# CAN_MUX.net
KiCad netlist of a schematic drawn in Altium Designer
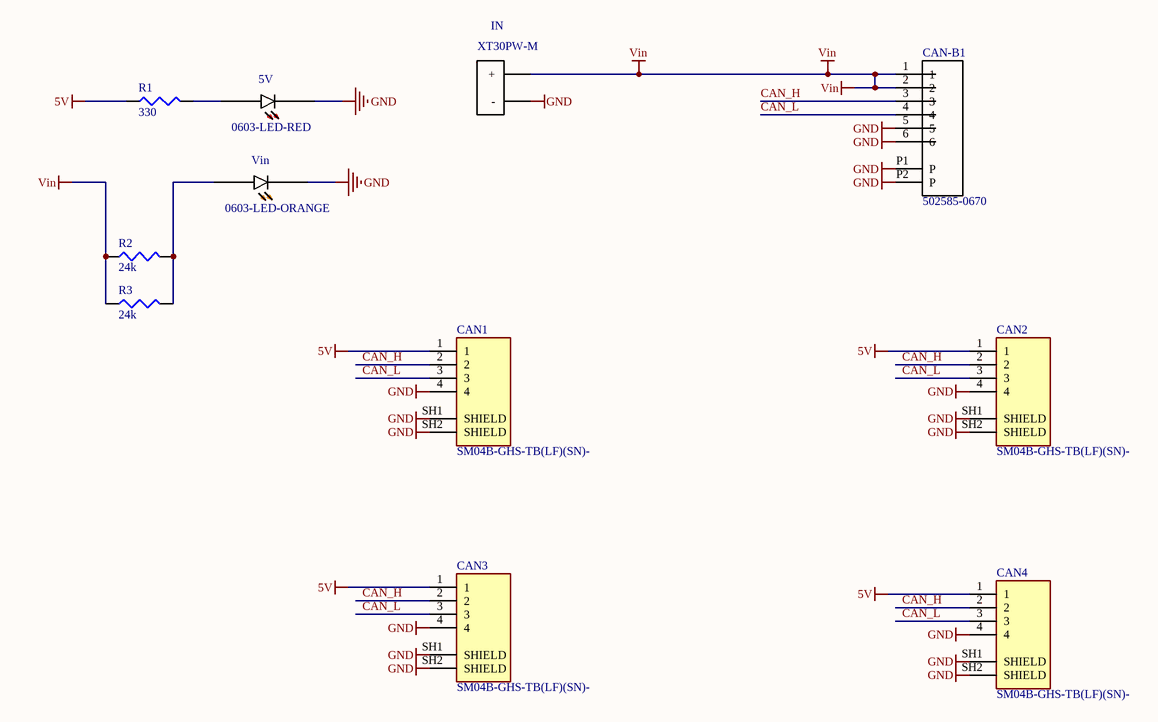
[diagram p0: CAN MUX.SchDoc]

(export (version "E")
  (design (tool "Eeschema 10.0.6"))
  (components
    (comp (ref "5V")
      (value "0603-LED-RED")
      (footprint "*LEDM1608X80_LTE-C1906R-14(Primary)")
      (description "Red 620nm LED Indication - Discrete 2.2V 0603 (1608 Metric)")
      (fields (field (name "MP") "LTST-C194KRKT"))
      (libsource (lib "lib") (part "0603-LED-RED"))
    )
    (comp (ref "CAN-B1")
      (value "502585-0670")
      (footprint "MOLEX_502585-0670")
      (fields (field (name "MF") "Molex"))
      (libsource (lib "lib") (part "502585-0670"))
    )
    (comp (ref "CAN1")
      (value "SM04B-GHS-TB(LF)(SN)-")
      (footprint "JST_SM04B-GHS-TB(LF)(SN)-")
      (description "Connector Header Surface Mount, Right Angle 4 position 0.049 _1.25mm_")
      (fields (field (name "MP") "SM04B-GHS-TB_LF__SN_-") (field (name "MF") "JST Sales"))
      (libsource (lib "lib") (part "SM04B-GHS-TB(LF)(SN)-"))
    )
    (comp (ref "CAN2")
      (value "SM04B-GHS-TB(LF)(SN)-")
      (footprint "JST_SM04B-GHS-TB(LF)(SN)-")
      (description "Connector Header Surface Mount, Right Angle 4 position 0.049 _1.25mm_")
      (fields (field (name "MP") "SM04B-GHS-TB_LF__SN_-") (field (name "MF") "JST Sales"))
      (libsource (lib "lib") (part "SM04B-GHS-TB(LF)(SN)-"))
    )
    (comp (ref "CAN3")
      (value "SM04B-GHS-TB(LF)(SN)-")
      (footprint "JST_SM04B-GHS-TB(LF)(SN)-")
      (description "Connector Header Surface Mount, Right Angle 4 position 0.049 _1.25mm_")
      (fields (field (name "MP") "SM04B-GHS-TB_LF__SN_-") (field (name "MF") "JST Sales"))
      (libsource (lib "lib") (part "SM04B-GHS-TB(LF)(SN)-"))
    )
    (comp (ref "CAN4")
      (value "SM04B-GHS-TB(LF)(SN)-")
      (footprint "JST_SM04B-GHS-TB(LF)(SN)-")
      (description "Connector Header Surface Mount, Right Angle 4 position 0.049 _1.25mm_")
      (fields (field (name "MP") "SM04B-GHS-TB_LF__SN_-") (field (name "MF") "JST Sales"))
      (libsource (lib "lib") (part "SM04B-GHS-TB(LF)(SN)-"))
    )
    (comp (ref "IN")
      (value "XT30PW-M")
      (footprint "XT30PW-M")
      (fields (field (name "MF") "AMASS"))
      (libsource (lib "lib") (part "XT30PW-M"))
    )
    (comp (ref "R1")
      (value "330")
      (footprint "J1-0603")
      (description "330 Ohms ±1% 0.1W, 1/10W Chip Resistor 0603 (1608 Metric) Thick Film")
      (fields (field (name "MF") "Yageo or NXP") (field (name "MP") "RC0603FR-07330RL"))
      (libsource (lib "lib") (part "RC0603FR-07330RL"))
    )
    (comp (ref "R2")
      (value "24k")
      (footprint "J1-0603")
      (description "24 kOhms ±1% 0.1W, 1/10W Chip Resistor 0603 (1608 Metric) Thick Film")
      (fields (field (name "MF") "Yageo or NXP") (field (name "MP") "RC0603FR-0724KL"))
      (libsource (lib "lib") (part "RC0603FR-0724KL"))
    )
    (comp (ref "R3")
      (value "24k")
      (footprint "J1-0603")
      (description "24 kOhms ±1% 0.1W, 1/10W Chip Resistor 0603 (1608 Metric) Thick Film")
      (fields (field (name "MF") "Yageo or NXP") (field (name "MP") "RC0603FR-0724KL"))
      (libsource (lib "lib") (part "RC0603FR-0724KL"))
    )
    (comp (ref "Vin")
      (value "0603-LED-ORANGE")
      (footprint "*LEDM1608X80_LTE-C1906R-14(Primary)")
      (description "Orange 605nm LED Indication - Discrete 2.2V 0603 (1608 Metric)")
      (fields (field (name "MP") "LTST-C194KFKT"))
      (libsource (lib "lib") (part "0603-LED-ORANGE"))
    )
  )
  (nets
    (net (code "1") (name "/CAN_H") (class "Default")
      (node (ref "CAN-B1") (pin "3") (pinfunction "3_3") (pintype "passive"))
      (node (ref "CAN1") (pin "2") (pinfunction "2_2") (pintype "passive"))
      (node (ref "CAN2") (pin "2") (pinfunction "2_2") (pintype "passive"))
      (node (ref "CAN3") (pin "2") (pinfunction "2_2") (pintype "passive"))
      (node (ref "CAN4") (pin "2") (pinfunction "2_2") (pintype "passive"))
    )
    (net (code "2") (name "/CAN_L") (class "Default")
      (node (ref "CAN-B1") (pin "4") (pinfunction "4_4") (pintype "passive"))
      (node (ref "CAN1") (pin "3") (pinfunction "3_3") (pintype "passive"))
      (node (ref "CAN2") (pin "3") (pinfunction "3_3") (pintype "passive"))
      (node (ref "CAN3") (pin "3") (pinfunction "3_3") (pintype "passive"))
      (node (ref "CAN4") (pin "3") (pinfunction "3_3") (pintype "passive"))
    )
    (net (code "3") (name "5V") (class "Default")
      (node (ref "CAN1") (pin "1") (pinfunction "1_1") (pintype "passive"))
      (node (ref "CAN2") (pin "1") (pinfunction "1_1") (pintype "passive"))
      (node (ref "CAN3") (pin "1") (pinfunction "1_1") (pintype "passive"))
      (node (ref "CAN4") (pin "1") (pinfunction "1_1") (pintype "passive"))
      (node (ref "R1") (pin "1") (pinfunction "1_1") (pintype "passive"))
    )
    (net (code "4") (name "GND") (class "Default")
      (node (ref "5V") (pin "C") (pinfunction "C_C") (pintype "passive"))
      (node (ref "CAN-B1") (pin "5") (pinfunction "5_5") (pintype "passive"))
      (node (ref "CAN-B1") (pin "6") (pinfunction "6_6") (pintype "passive"))
      (node (ref "CAN-B1") (pin "P1") (pinfunction "P_P1") (pintype "passive"))
      (node (ref "CAN-B1") (pin "P2") (pinfunction "P_P2") (pintype "passive"))
      (node (ref "CAN1") (pin "4") (pinfunction "4_4") (pintype "passive"))
      (node (ref "CAN1") (pin "SH1") (pinfunction "SHIELD_SH1") (pintype "power_in"))
      (node (ref "CAN1") (pin "SH2") (pinfunction "SHIELD_SH2") (pintype "power_in"))
      (node (ref "CAN2") (pin "4") (pinfunction "4_4") (pintype "passive"))
      (node (ref "CAN2") (pin "SH1") (pinfunction "SHIELD_SH1") (pintype "power_in"))
      (node (ref "CAN2") (pin "SH2") (pinfunction "SHIELD_SH2") (pintype "power_in"))
      (node (ref "CAN3") (pin "4") (pinfunction "4_4") (pintype "passive"))
      (node (ref "CAN3") (pin "SH1") (pinfunction "SHIELD_SH1") (pintype "power_in"))
      (node (ref "CAN3") (pin "SH2") (pinfunction "SHIELD_SH2") (pintype "power_in"))
      (node (ref "CAN4") (pin "4") (pinfunction "4_4") (pintype "passive"))
      (node (ref "CAN4") (pin "SH1") (pinfunction "SHIELD_SH1") (pintype "power_in"))
      (node (ref "CAN4") (pin "SH2") (pinfunction "SHIELD_SH2") (pintype "power_in"))
      (node (ref "IN") (pin "MINUS") (pinfunction "-_MINUS") (pintype "passive"))
      (node (ref "Vin") (pin "C") (pinfunction "C_C") (pintype "passive"))
    )
    (net (code "5") (name "Net-(5V-PadA)") (class "Default")
      (node (ref "5V") (pin "A") (pinfunction "A_A") (pintype "passive"))
      (node (ref "R1") (pin "2") (pinfunction "2_2") (pintype "passive"))
    )
    (net (code "6") (name "Net-(R2-Pad2)") (class "Default")
      (node (ref "R2") (pin "2") (pinfunction "2_2") (pintype "passive"))
      (node (ref "R3") (pin "2") (pinfunction "2_2") (pintype "passive"))
      (node (ref "Vin") (pin "A") (pinfunction "A_A") (pintype "passive"))
    )
    (net (code "7") (name "Vin") (class "Default")
      (node (ref "CAN-B1") (pin "1") (pinfunction "1_1") (pintype "passive"))
      (node (ref "CAN-B1") (pin "2") (pinfunction "2_2") (pintype "passive"))
      (node (ref "IN") (pin "PLUS") (pinfunction "+_PLUS") (pintype "passive"))
      (node (ref "R2") (pin "1") (pinfunction "1_1") (pintype "passive"))
      (node (ref "R3") (pin "1") (pinfunction "1_1") (pintype "passive"))
    )
  )
)
